# AlcoholDetectie_V2.net
KiCad netlist of a schematic drawn in Altium Designer
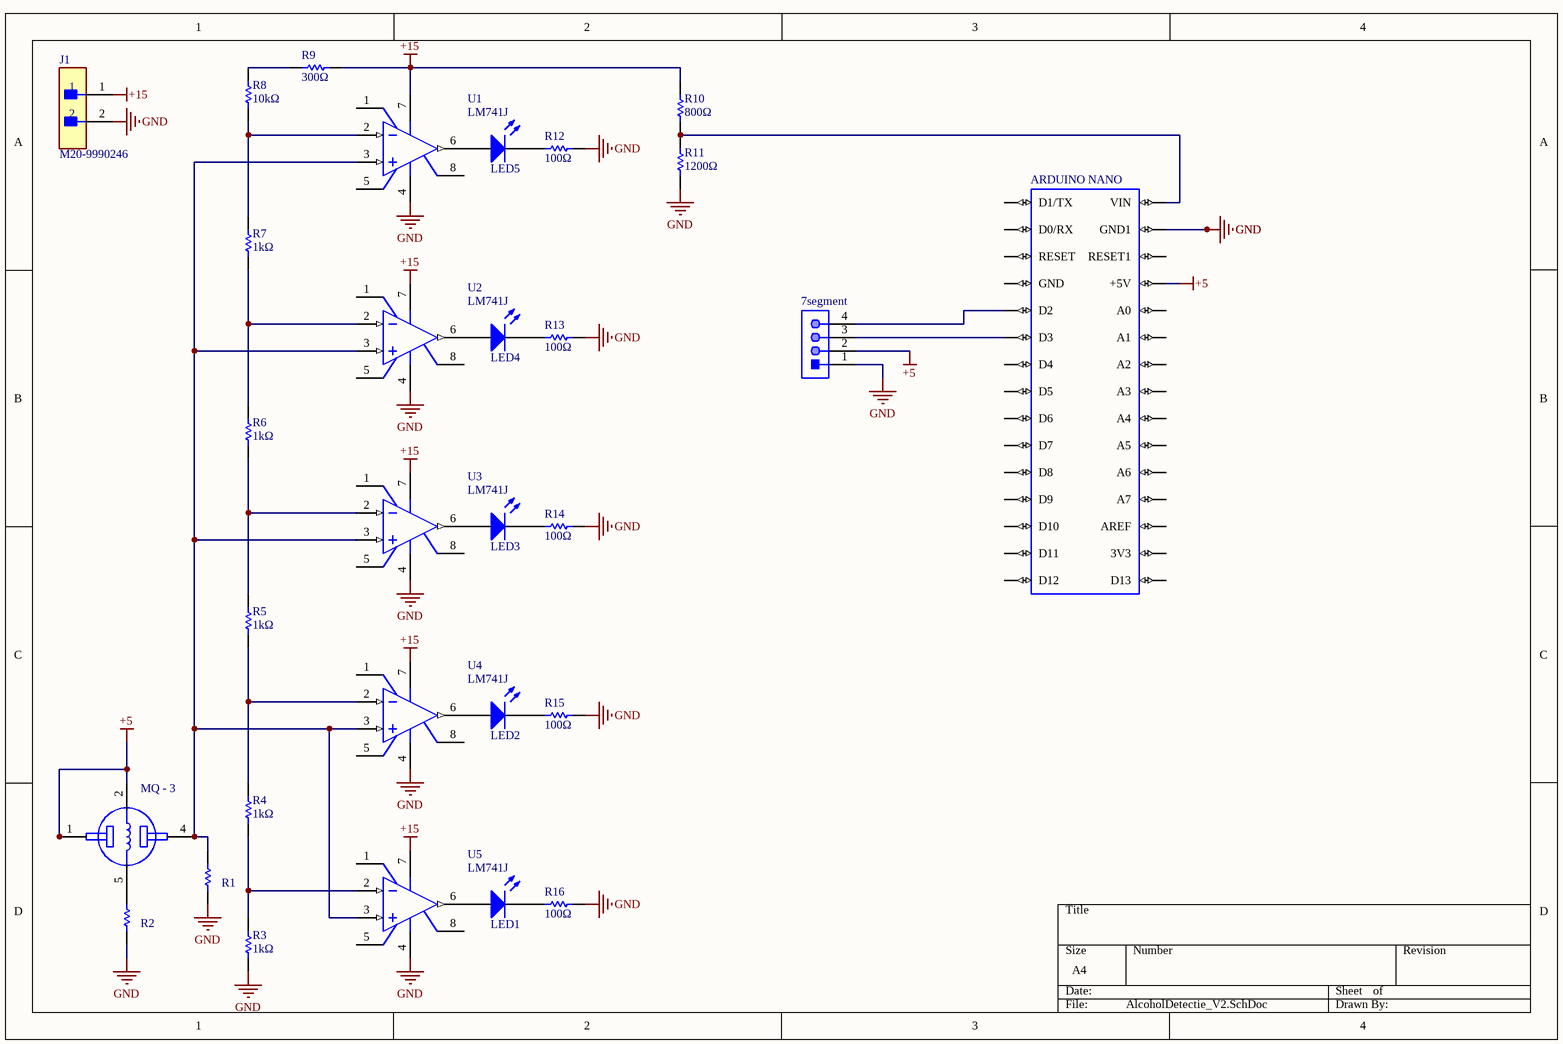
[diagram p0: AlcoholDetectie_V2.SchDoc]

(export (version "E")
  (design (tool "Eeschema 10.0.6"))
  (components
    (comp (ref "7segment")
      (value "61300411121")
      (footprint "61300411121")
      (description "THT Vertical Pin Header WR-PHD, Pitch 2.54 mm, Single Row, 4 pins")
      (fields (field (name "MANUFACTURER") "Wurth Elektronik") (field (name "PUBLISHER") "WurthElektronik"))
      (libsource (lib "Altium Content Vault") (part "WE-CN-1P-M-R4"))
    )
    (comp (ref "ARDUINO NANO")
      (value "ARDUINONANO")
      (footprint "PDIP-32")
      (description "Arduino; 20MHz; 3.3Ã·5VDC; Flash: 32kB; SRAM: 2kB; ATMEGA328,FT232R")
      (fields (field (name "MF") "Arduino"))
      (libsource (lib "ARDUINONANO") (part "ARDUINONANO"))
    )
    (comp (ref "GROEN")
      (value "LED1")
      (footprint "LED-1")
      (description "Typical RED GaAs LED")
      (fields (field (name "PUBLISHER") "Altium Limited"))
      (libsource (lib "Miscellaneous Devices") (part "LED1"))
    )
    (comp (ref "J1")
      (value "M20-9990246")
      (footprint "FP-M20-9990246-MFG")
      (description "CONN HEADER VERT 2POS 2.54MM")
      (fields
        (field (name "OCTOPART") "https://octopart.com/m20-9990246-harwin-2590635")
        (field (name "MANUFACTURER") "Harwin")
      )
      (libsource (lib "Altium Content Vault") (part "3bc925449376181038e59eaffc5286c"))
    )
    (comp (ref "MQ - 3")
      (value "SEN-08880")
      (footprint "XDCR_SEN-08880")
      (description "Alcohol _C2H6O_ Sensor 0 V ~ 3.3 V")
      (fields (field (name "MF") "SparkFun Electronics"))
      (libsource (lib "SEN-08880") (part "SEN-08880"))
    )
    (comp (ref "ORANJE_1")
      (value "LED2")
      (footprint "LED-1")
      (description "Typical RED GaAs LED")
      (fields (field (name "PUBLISHER") "Altium Limited"))
      (libsource (lib "Miscellaneous Devices") (part "LED1"))
    )
    (comp (ref "ORANJE_2")
      (value "LED3")
      (footprint "LED-1")
      (description "Typical RED GaAs LED")
      (fields (field (name "PUBLISHER") "Altium Limited"))
      (libsource (lib "Miscellaneous Devices") (part "LED1"))
    )
    (comp (ref "R1")
      (value "1k Ω")
      (footprint "RESC2013X50X30LL20T20")
      (fields (field (name "MANUFACTURER") "Vishay Dale") (field (name "PART NUMBER") "CRCW08050000Z0EA"))
      (libsource (lib "Altium Content Vault") (part "RES"))
    )
    (comp (ref "R2")
      (value "5,1 Ω")
      (footprint "RESC2013X50X30LL20T20")
      (fields (field (name "MANUFACTURER") "Vishay Dale") (field (name "PART NUMBER") "CRCW08050000Z0EA"))
      (libsource (lib "Altium Content Vault") (part "RES"))
    )
    (comp (ref "R3")
      (value "1kΩ")
      (footprint "RESC2013X50X30LL20T20")
      (fields (field (name "MANUFACTURER") "Vishay Dale") (field (name "PART NUMBER") "CRCW08050000Z0EA"))
      (libsource (lib "Altium Content Vault") (part "RES"))
    )
    (comp (ref "R4")
      (value "1kΩ")
      (footprint "RESC2013X50X30LL20T20")
      (fields (field (name "MANUFACTURER") "Vishay Dale") (field (name "PART NUMBER") "CRCW08050000Z0EA"))
      (libsource (lib "Altium Content Vault") (part "RES"))
    )
    (comp (ref "R5")
      (value "1kΩ")
      (footprint "RESC2013X50X30LL20T20")
      (fields (field (name "MANUFACTURER") "Vishay Dale") (field (name "PART NUMBER") "CRCW08050000Z0EA"))
      (libsource (lib "Altium Content Vault") (part "RES"))
    )
    (comp (ref "R6")
      (value "1kΩ")
      (footprint "RESC2013X50X30LL20T20")
      (fields (field (name "MANUFACTURER") "Vishay Dale") (field (name "PART NUMBER") "CRCW08050000Z0EA"))
      (libsource (lib "Altium Content Vault") (part "RES"))
    )
    (comp (ref "R7")
      (value "1kΩ")
      (footprint "RESC2013X50X30LL20T20")
      (fields (field (name "MANUFACTURER") "Vishay Dale") (field (name "PART NUMBER") "CRCW08050000Z0EA"))
      (libsource (lib "Altium Content Vault") (part "RES"))
    )
    (comp (ref "R8")
      (value "10kΩ")
      (footprint "RESC2013X50X30LL20T20")
      (fields (field (name "MANUFACTURER") "Vishay Dale") (field (name "PART NUMBER") "CRCW08050000Z0EA"))
      (libsource (lib "Altium Content Vault") (part "RES"))
    )
    (comp (ref "R9")
      (value "300Ω")
      (footprint "RESC2013X50X30LL20T20")
      (fields (field (name "MANUFACTURER") "Vishay Dale") (field (name "PART NUMBER") "CRCW08050000Z0EA"))
      (libsource (lib "Altium Content Vault") (part "RES"))
    )
    (comp (ref "R10")
      (value "800Ω")
      (footprint "RESC2013X50X30LL20T20")
      (fields (field (name "MANUFACTURER") "Vishay Dale") (field (name "PART NUMBER") "CRCW08050000Z0EA"))
      (libsource (lib "Altium Content Vault") (part "RES"))
    )
    (comp (ref "R11")
      (value "1200Ω")
      (footprint "RESC2013X50X30LL20T20")
      (fields (field (name "MANUFACTURER") "Vishay Dale") (field (name "PART NUMBER") "CRCW08050000Z0EA"))
      (libsource (lib "Altium Content Vault") (part "RES"))
    )
    (comp (ref "R12")
      (value "100Ω")
      (footprint "RESC2013X50X30LL20T20")
      (fields (field (name "MANUFACTURER") "Vishay Dale") (field (name "PART NUMBER") "CRCW08050000Z0EA"))
      (libsource (lib "Altium Content Vault") (part "RES"))
    )
    (comp (ref "R13")
      (value "100Ω")
      (footprint "RESC2013X50X30LL20T20")
      (fields (field (name "MANUFACTURER") "Vishay Dale") (field (name "PART NUMBER") "CRCW08050000Z0EA"))
      (libsource (lib "Altium Content Vault") (part "RES"))
    )
    (comp (ref "R14")
      (value "100Ω")
      (footprint "RESC2013X50X30LL20T20")
      (fields (field (name "MANUFACTURER") "Vishay Dale") (field (name "PART NUMBER") "CRCW08050000Z0EA"))
      (libsource (lib "Altium Content Vault") (part "RES"))
    )
    (comp (ref "R15")
      (value "100Ω")
      (footprint "RESC2013X50X30LL20T20")
      (fields (field (name "MANUFACTURER") "Vishay Dale") (field (name "PART NUMBER") "CRCW08050000Z0EA"))
      (libsource (lib "Altium Content Vault") (part "RES"))
    )
    (comp (ref "R16")
      (value "100Ω")
      (footprint "RESC2013X50X30LL20T20")
      (fields (field (name "MANUFACTURER") "Vishay Dale") (field (name "PART NUMBER") "CRCW08050000Z0EA"))
      (libsource (lib "Altium Content Vault") (part "RES"))
    )
    (comp (ref "ROOD_1")
      (value "LED4")
      (footprint "LED-1")
      (description "Typical RED GaAs LED")
      (fields (field (name "PUBLISHER") "Altium Limited"))
      (libsource (lib "Miscellaneous Devices") (part "LED1"))
    )
    (comp (ref "ROOD_2")
      (value "LED5")
      (footprint "LED-1")
      (description "Typical RED GaAs LED")
      (fields (field (name "PUBLISHER") "Altium Limited"))
      (libsource (lib "Miscellaneous Devices") (part "LED1"))
    )
    (comp (ref "U1")
      (value "LM741J")
      (footprint "NAB0008A")
      (description "Operational Amplifier, 8-pin CerDIP")
      (fields (field (name "MANUFACTURER") "Texas Instruments"))
      (libsource (lib "Altium Content Vault") (part "AMP-OPA-LM741-8"))
    )
    (comp (ref "U2")
      (value "LM741J")
      (footprint "NAB0008A")
      (description "Operational Amplifier, 8-pin CerDIP")
      (fields (field (name "MANUFACTURER") "Texas Instruments"))
      (libsource (lib "Altium Content Vault") (part "AMP-OPA-LM741-8"))
    )
    (comp (ref "U3")
      (value "LM741J")
      (footprint "NAB0008A")
      (description "Operational Amplifier, 8-pin CerDIP")
      (fields (field (name "MANUFACTURER") "Texas Instruments"))
      (libsource (lib "Altium Content Vault") (part "AMP-OPA-LM741-8"))
    )
    (comp (ref "U4")
      (value "LM741J")
      (footprint "NAB0008A")
      (description "Operational Amplifier, 8-pin CerDIP")
      (fields (field (name "MANUFACTURER") "Texas Instruments"))
      (libsource (lib "Altium Content Vault") (part "AMP-OPA-LM741-8"))
    )
    (comp (ref "U5")
      (value "LM741J")
      (footprint "NAB0008A")
      (description "Operational Amplifier, 8-pin CerDIP")
      (fields (field (name "MANUFACTURER") "Texas Instruments"))
      (libsource (lib "Altium Content Vault") (part "AMP-OPA-LM741-8"))
    )
  )
  (nets
    (net (code "1") (name "+5") (class "Default")
      (node (ref "7segment") (pin "2") (pinfunction "2_2") (pintype "passive"))
      (node (ref "ARDUINO NANO") (pin "+5V") (pinfunction "+5V_+5V") (pintype "bidirectional"))
      (node (ref "MQ - 3") (pin "1") (pinfunction "A_1") (pintype "passive"))
      (node (ref "MQ - 3") (pin "2") (pinfunction "H1_2") (pintype "passive"))
      (node (ref "MQ - 3") (pin "3") (pinfunction "A_3") (pintype "passive"))
    )
    (net (code "2") (name "+15") (class "Default")
      (node (ref "J1") (pin "1") (pinfunction "1_1") (pintype "passive"))
      (node (ref "R10") (pin "1") (pinfunction "1_1") (pintype "passive"))
      (node (ref "R9") (pin "1") (pinfunction "1_1") (pintype "passive"))
      (node (ref "U1") (pin "7") (pinfunction "V+_7") (pintype "power_in"))
      (node (ref "U2") (pin "7") (pinfunction "V+_7") (pintype "power_in"))
      (node (ref "U3") (pin "7") (pinfunction "V+_7") (pintype "power_in"))
      (node (ref "U4") (pin "7") (pinfunction "V+_7") (pintype "power_in"))
      (node (ref "U5") (pin "7") (pinfunction "V+_7") (pintype "power_in"))
    )
    (net (code "3") (name "GND") (class "Default")
      (node (ref "7segment") (pin "1") (pinfunction "1_1") (pintype "passive"))
      (node (ref "ARDUINO NANO") (pin "GND1") (pinfunction "GND1_GND1") (pintype "bidirectional"))
      (node (ref "J1") (pin "2") (pinfunction "2_2") (pintype "passive"))
      (node (ref "R1") (pin "1") (pinfunction "1_1") (pintype "passive"))
      (node (ref "R11") (pin "1") (pinfunction "1_1") (pintype "passive"))
      (node (ref "R12") (pin "1") (pinfunction "1_1") (pintype "passive"))
      (node (ref "R13") (pin "1") (pinfunction "1_1") (pintype "passive"))
      (node (ref "R14") (pin "1") (pinfunction "1_1") (pintype "passive"))
      (node (ref "R15") (pin "1") (pinfunction "1_1") (pintype "passive"))
      (node (ref "R16") (pin "1") (pinfunction "1_1") (pintype "passive"))
      (node (ref "R2") (pin "1") (pinfunction "1_1") (pintype "passive"))
      (node (ref "R3") (pin "1") (pinfunction "1_1") (pintype "passive"))
      (node (ref "U1") (pin "4") (pinfunction "V-_4") (pintype "power_in"))
      (node (ref "U2") (pin "4") (pinfunction "V-_4") (pintype "power_in"))
      (node (ref "U3") (pin "4") (pinfunction "V-_4") (pintype "power_in"))
      (node (ref "U4") (pin "4") (pinfunction "V-_4") (pintype "power_in"))
      (node (ref "U5") (pin "4") (pinfunction "V-_4") (pintype "power_in"))
    )
    (net (code "4") (name "Net-(7segment-Pad3)") (class "Default")
      (node (ref "7segment") (pin "3") (pinfunction "3_3") (pintype "passive"))
      (node (ref "ARDUINO NANO") (pin "D3") (pinfunction "D3_D3") (pintype "bidirectional"))
    )
    (net (code "5") (name "Net-(7segment-Pad4)") (class "Default")
      (node (ref "7segment") (pin "4") (pinfunction "4_4") (pintype "passive"))
      (node (ref "ARDUINO NANO") (pin "D2") (pinfunction "D2_D2") (pintype "bidirectional"))
    )
    (net (code "6") (name "Net-(ARDUINO NANO-PadVIN)") (class "Default")
      (node (ref "ARDUINO NANO") (pin "VIN") (pinfunction "VIN_VIN") (pintype "bidirectional"))
      (node (ref "R10") (pin "2") (pinfunction "2_2") (pintype "passive"))
      (node (ref "R11") (pin "2") (pinfunction "2_2") (pintype "passive"))
    )
    (net (code "7") (name "Net-(GROEN-A)") (class "Default")
      (node (ref "GROEN") (pin "1") (pinfunction "A_1") (pintype "passive"))
      (node (ref "U5") (pin "6") (pinfunction "OUT_6") (pintype "output"))
    )
    (net (code "8") (name "Net-(GROEN-K)") (class "Default")
      (node (ref "GROEN") (pin "2") (pinfunction "K_2") (pintype "passive"))
      (node (ref "R16") (pin "2") (pinfunction "2_2") (pintype "passive"))
    )
    (net (code "9") (name "Net-(MQ - 3-H2)") (class "Default")
      (node (ref "MQ - 3") (pin "5") (pinfunction "H2_5") (pintype "passive"))
      (node (ref "R2") (pin "2") (pinfunction "2_2") (pintype "passive"))
    )
    (net (code "10") (name "Net-(ORANJE_1-A)") (class "Default")
      (node (ref "ORANJE_1") (pin "1") (pinfunction "A_1") (pintype "passive"))
      (node (ref "U4") (pin "6") (pinfunction "OUT_6") (pintype "output"))
    )
    (net (code "11") (name "Net-(ORANJE_1-K)") (class "Default")
      (node (ref "ORANJE_1") (pin "2") (pinfunction "K_2") (pintype "passive"))
      (node (ref "R15") (pin "2") (pinfunction "2_2") (pintype "passive"))
    )
    (net (code "12") (name "Net-(ORANJE_2-A)") (class "Default")
      (node (ref "ORANJE_2") (pin "1") (pinfunction "A_1") (pintype "passive"))
      (node (ref "U3") (pin "6") (pinfunction "OUT_6") (pintype "output"))
    )
    (net (code "13") (name "Net-(ORANJE_2-K)") (class "Default")
      (node (ref "ORANJE_2") (pin "2") (pinfunction "K_2") (pintype "passive"))
      (node (ref "R14") (pin "2") (pinfunction "2_2") (pintype "passive"))
    )
    (net (code "14") (name "Net-(R8-Pad2)") (class "Default")
      (node (ref "R8") (pin "2") (pinfunction "2_2") (pintype "passive"))
      (node (ref "R9") (pin "2") (pinfunction "2_2") (pintype "passive"))
    )
    (net (code "15") (name "Net-(ROOD_1-A)") (class "Default")
      (node (ref "ROOD_1") (pin "1") (pinfunction "A_1") (pintype "passive"))
      (node (ref "U2") (pin "6") (pinfunction "OUT_6") (pintype "output"))
    )
    (net (code "16") (name "Net-(ROOD_1-K)") (class "Default")
      (node (ref "R13") (pin "2") (pinfunction "2_2") (pintype "passive"))
      (node (ref "ROOD_1") (pin "2") (pinfunction "K_2") (pintype "passive"))
    )
    (net (code "17") (name "Net-(ROOD_2-A)") (class "Default")
      (node (ref "ROOD_2") (pin "1") (pinfunction "A_1") (pintype "passive"))
      (node (ref "U1") (pin "6") (pinfunction "OUT_6") (pintype "output"))
    )
    (net (code "18") (name "Net-(ROOD_2-K)") (class "Default")
      (node (ref "R12") (pin "2") (pinfunction "2_2") (pintype "passive"))
      (node (ref "ROOD_2") (pin "2") (pinfunction "K_2") (pintype "passive"))
    )
    (net (code "19") (name "Net-(U1-IN+)") (class "Default")
      (node (ref "MQ - 3") (pin "4") (pinfunction "B_4") (pintype "passive"))
      (node (ref "MQ - 3") (pin "6") (pinfunction "B_6") (pintype "passive"))
      (node (ref "R1") (pin "2") (pinfunction "2_2") (pintype "passive"))
      (node (ref "U1") (pin "3") (pinfunction "IN+_3") (pintype "input"))
      (node (ref "U2") (pin "3") (pinfunction "IN+_3") (pintype "input"))
      (node (ref "U3") (pin "3") (pinfunction "IN+_3") (pintype "input"))
      (node (ref "U4") (pin "3") (pinfunction "IN+_3") (pintype "input"))
      (node (ref "U5") (pin "3") (pinfunction "IN+_3") (pintype "input"))
    )
    (net (code "20") (name "Net-(U1-IN-)") (class "Default")
      (node (ref "R7") (pin "2") (pinfunction "2_2") (pintype "passive"))
      (node (ref "R8") (pin "1") (pinfunction "1_1") (pintype "passive"))
      (node (ref "U1") (pin "2") (pinfunction "IN-_2") (pintype "input"))
    )
    (net (code "21") (name "Net-(U2-IN-)") (class "Default")
      (node (ref "R6") (pin "2") (pinfunction "2_2") (pintype "passive"))
      (node (ref "R7") (pin "1") (pinfunction "1_1") (pintype "passive"))
      (node (ref "U2") (pin "2") (pinfunction "IN-_2") (pintype "input"))
    )
    (net (code "22") (name "Net-(U3-IN-)") (class "Default")
      (node (ref "R5") (pin "2") (pinfunction "2_2") (pintype "passive"))
      (node (ref "R6") (pin "1") (pinfunction "1_1") (pintype "passive"))
      (node (ref "U3") (pin "2") (pinfunction "IN-_2") (pintype "input"))
    )
    (net (code "23") (name "Net-(U4-IN-)") (class "Default")
      (node (ref "R4") (pin "2") (pinfunction "2_2") (pintype "passive"))
      (node (ref "R5") (pin "1") (pinfunction "1_1") (pintype "passive"))
      (node (ref "U4") (pin "2") (pinfunction "IN-_2") (pintype "input"))
    )
    (net (code "24") (name "Net-(U5-IN-)") (class "Default")
      (node (ref "R3") (pin "2") (pinfunction "2_2") (pintype "passive"))
      (node (ref "R4") (pin "1") (pinfunction "1_1") (pintype "passive"))
      (node (ref "U5") (pin "2") (pinfunction "IN-_2") (pintype "input"))
    )
    (net (code "25") (name "unconnected-(ARDUINO NANO-Pad3V3)") (class "Default")
      (node (ref "ARDUINO NANO") (pin "3V3") (pinfunction "3V3_3V3") (pintype "bidirectional"))
    )
    (net (code "26") (name "unconnected-(ARDUINO NANO-PadA0)") (class "Default")
      (node (ref "ARDUINO NANO") (pin "A0") (pinfunction "A0_A0") (pintype "bidirectional"))
    )
    (net (code "27") (name "unconnected-(ARDUINO NANO-PadA1)") (class "Default")
      (node (ref "ARDUINO NANO") (pin "A1") (pinfunction "A1_A1") (pintype "bidirectional"))
    )
    (net (code "28") (name "unconnected-(ARDUINO NANO-PadA2)") (class "Default")
      (node (ref "ARDUINO NANO") (pin "A2") (pinfunction "A2_A2") (pintype "bidirectional"))
    )
    (net (code "29") (name "unconnected-(ARDUINO NANO-PadA3)") (class "Default")
      (node (ref "ARDUINO NANO") (pin "A3") (pinfunction "A3_A3") (pintype "bidirectional"))
    )
    (net (code "30") (name "unconnected-(ARDUINO NANO-PadA4)") (class "Default")
      (node (ref "ARDUINO NANO") (pin "A4") (pinfunction "A4_A4") (pintype "bidirectional"))
    )
    (net (code "31") (name "unconnected-(ARDUINO NANO-PadA5)") (class "Default")
      (node (ref "ARDUINO NANO") (pin "A5") (pinfunction "A5_A5") (pintype "bidirectional"))
    )
    (net (code "32") (name "unconnected-(ARDUINO NANO-PadA6)") (class "Default")
      (node (ref "ARDUINO NANO") (pin "A6") (pinfunction "A6_A6") (pintype "bidirectional"))
    )
    (net (code "33") (name "unconnected-(ARDUINO NANO-PadA7)") (class "Default")
      (node (ref "ARDUINO NANO") (pin "A7") (pinfunction "A7_A7") (pintype "bidirectional"))
    )
    (net (code "34") (name "unconnected-(ARDUINO NANO-PadAREF)") (class "Default")
      (node (ref "ARDUINO NANO") (pin "AREF") (pinfunction "AREF_AREF") (pintype "bidirectional"))
    )
    (net (code "35") (name "unconnected-(ARDUINO NANO-PadD0{slash}RX)") (class "Default")
      (node (ref "ARDUINO NANO") (pin "D0/RX") (pinfunction "D0/RX_D0/RX") (pintype "bidirectional"))
    )
    (net (code "36") (name "unconnected-(ARDUINO NANO-PadD1{slash}TX)") (class "Default")
      (node (ref "ARDUINO NANO") (pin "D1/TX") (pinfunction "D1/TX_D1/TX") (pintype "bidirectional"))
    )
    (net (code "37") (name "unconnected-(ARDUINO NANO-PadD4)") (class "Default")
      (node (ref "ARDUINO NANO") (pin "D4") (pinfunction "D4_D4") (pintype "bidirectional"))
    )
    (net (code "38") (name "unconnected-(ARDUINO NANO-PadD5)") (class "Default")
      (node (ref "ARDUINO NANO") (pin "D5") (pinfunction "D5_D5") (pintype "bidirectional"))
    )
    (net (code "39") (name "unconnected-(ARDUINO NANO-PadD6)") (class "Default")
      (node (ref "ARDUINO NANO") (pin "D6") (pinfunction "D6_D6") (pintype "bidirectional"))
    )
    (net (code "40") (name "unconnected-(ARDUINO NANO-PadD7)") (class "Default")
      (node (ref "ARDUINO NANO") (pin "D7") (pinfunction "D7_D7") (pintype "bidirectional"))
    )
    (net (code "41") (name "unconnected-(ARDUINO NANO-PadD8)") (class "Default")
      (node (ref "ARDUINO NANO") (pin "D8") (pinfunction "D8_D8") (pintype "bidirectional"))
    )
    (net (code "42") (name "unconnected-(ARDUINO NANO-PadD9)") (class "Default")
      (node (ref "ARDUINO NANO") (pin "D9") (pinfunction "D9_D9") (pintype "bidirectional"))
    )
    (net (code "43") (name "unconnected-(ARDUINO NANO-PadD10)") (class "Default")
      (node (ref "ARDUINO NANO") (pin "D10") (pinfunction "D10_D10") (pintype "bidirectional"))
    )
    (net (code "44") (name "unconnected-(ARDUINO NANO-PadD11)") (class "Default")
      (node (ref "ARDUINO NANO") (pin "D11") (pinfunction "D11_D11") (pintype "bidirectional"))
    )
    (net (code "45") (name "unconnected-(ARDUINO NANO-PadD12)") (class "Default")
      (node (ref "ARDUINO NANO") (pin "D12") (pinfunction "D12_D12") (pintype "bidirectional"))
    )
    (net (code "46") (name "unconnected-(ARDUINO NANO-PadD13)") (class "Default")
      (node (ref "ARDUINO NANO") (pin "D13") (pinfunction "D13_D13") (pintype "bidirectional"))
    )
    (net (code "47") (name "unconnected-(ARDUINO NANO-PadGND)") (class "Default")
      (node (ref "ARDUINO NANO") (pin "GND") (pinfunction "GND_GND") (pintype "bidirectional"))
    )
    (net (code "48") (name "unconnected-(ARDUINO NANO-PadRESET)") (class "Default")
      (node (ref "ARDUINO NANO") (pin "RESET") (pinfunction "RESET_RESET") (pintype "bidirectional"))
    )
    (net (code "49") (name "unconnected-(ARDUINO NANO-PadRESET1)") (class "Default")
      (node (ref "ARDUINO NANO") (pin "RESET1") (pinfunction "RESET1_RESET1") (pintype "bidirectional"))
    )
    (net (code "50") (name "unconnected-(U1-NC-Pad8)") (class "Default")
      (node (ref "U1") (pin "8") (pinfunction "NC_8") (pintype "passive"))
    )
    (net (code "51") (name "unconnected-(U1-OFS_NULL-Pad1)") (class "Default")
      (node (ref "U1") (pin "1") (pinfunction "OFS_NULL_1") (pintype "passive"))
    )
    (net (code "52") (name "unconnected-(U1-OFS_NULL-Pad5)") (class "Default")
      (node (ref "U1") (pin "5") (pinfunction "OFS_NULL_5") (pintype "passive"))
    )
    (net (code "53") (name "unconnected-(U2-NC-Pad8)") (class "Default")
      (node (ref "U2") (pin "8") (pinfunction "NC_8") (pintype "passive"))
    )
    (net (code "54") (name "unconnected-(U2-OFS_NULL-Pad1)") (class "Default")
      (node (ref "U2") (pin "1") (pinfunction "OFS_NULL_1") (pintype "passive"))
    )
    (net (code "55") (name "unconnected-(U2-OFS_NULL-Pad5)") (class "Default")
      (node (ref "U2") (pin "5") (pinfunction "OFS_NULL_5") (pintype "passive"))
    )
    (net (code "56") (name "unconnected-(U3-NC-Pad8)") (class "Default")
      (node (ref "U3") (pin "8") (pinfunction "NC_8") (pintype "passive"))
    )
    (net (code "57") (name "unconnected-(U3-OFS_NULL-Pad1)") (class "Default")
      (node (ref "U3") (pin "1") (pinfunction "OFS_NULL_1") (pintype "passive"))
    )
    (net (code "58") (name "unconnected-(U3-OFS_NULL-Pad5)") (class "Default")
      (node (ref "U3") (pin "5") (pinfunction "OFS_NULL_5") (pintype "passive"))
    )
    (net (code "59") (name "unconnected-(U4-NC-Pad8)") (class "Default")
      (node (ref "U4") (pin "8") (pinfunction "NC_8") (pintype "passive"))
    )
    (net (code "60") (name "unconnected-(U4-OFS_NULL-Pad1)") (class "Default")
      (node (ref "U4") (pin "1") (pinfunction "OFS_NULL_1") (pintype "passive"))
    )
    (net (code "61") (name "unconnected-(U4-OFS_NULL-Pad5)") (class "Default")
      (node (ref "U4") (pin "5") (pinfunction "OFS_NULL_5") (pintype "passive"))
    )
    (net (code "62") (name "unconnected-(U5-NC-Pad8)") (class "Default")
      (node (ref "U5") (pin "8") (pinfunction "NC_8") (pintype "passive"))
    )
    (net (code "63") (name "unconnected-(U5-OFS_NULL-Pad1)") (class "Default")
      (node (ref "U5") (pin "1") (pinfunction "OFS_NULL_1") (pintype "passive"))
    )
    (net (code "64") (name "unconnected-(U5-OFS_NULL-Pad5)") (class "Default")
      (node (ref "U5") (pin "5") (pinfunction "OFS_NULL_5") (pintype "passive"))
    )
  )
)
